# Microcontrolador.net
KiCad netlist of a schematic drawn in Altium Designer
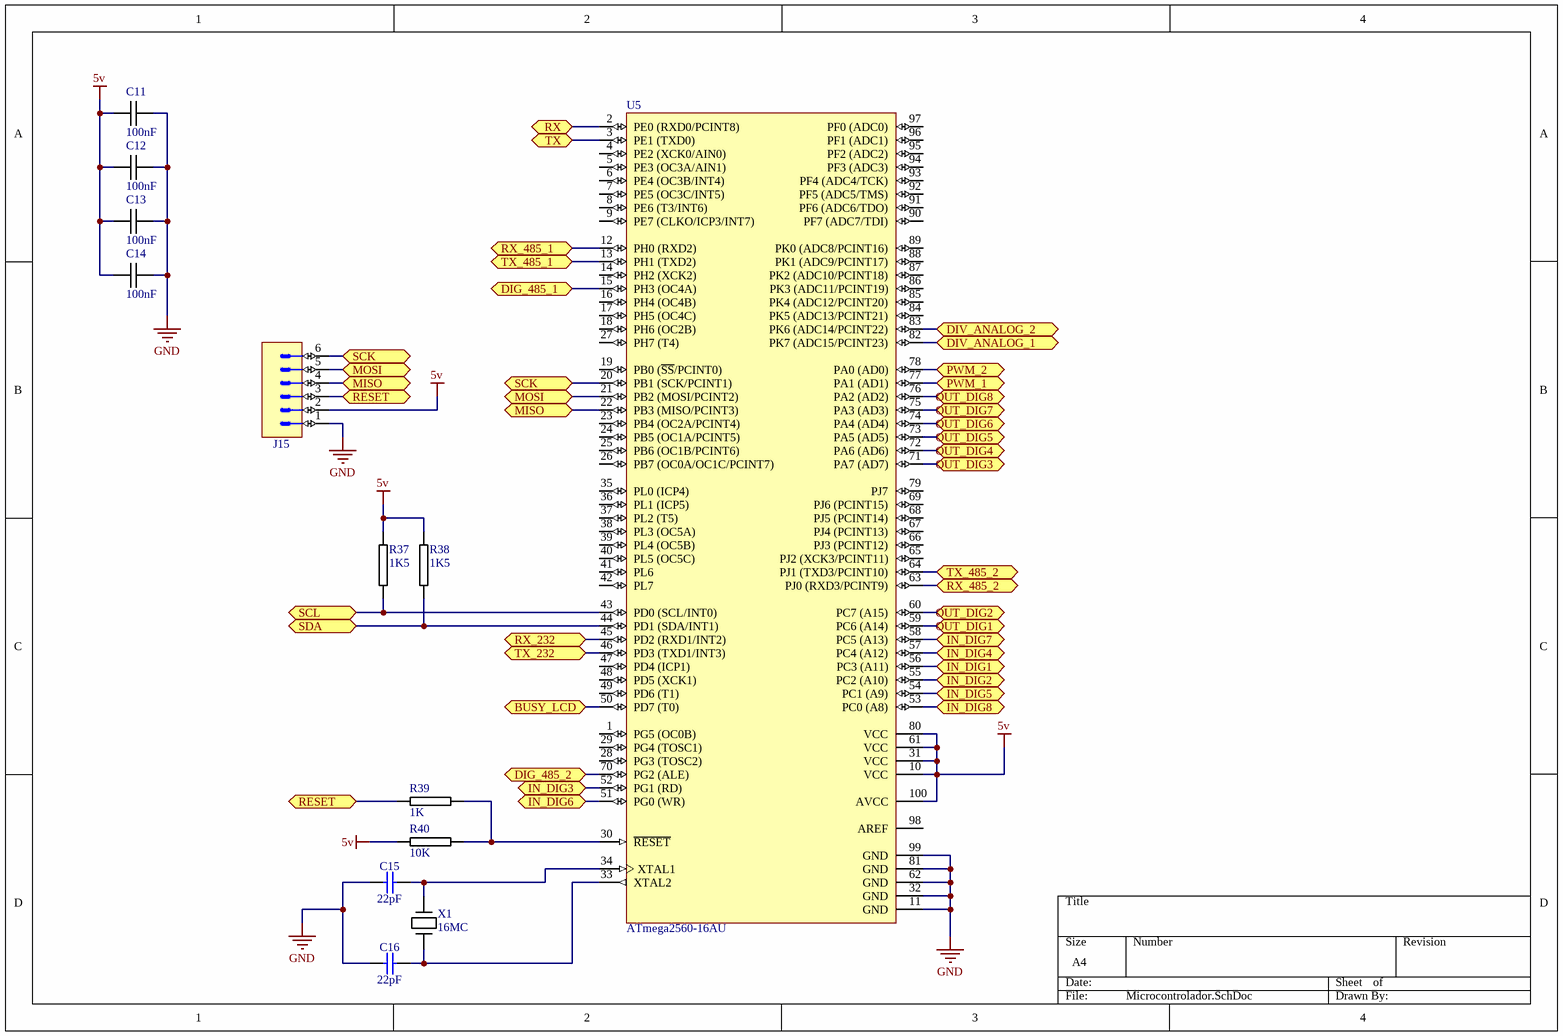
[diagram p0: Microcontrolador.SchDoc]

(export (version "E")
  (design (tool "Eeschema 10.0.6"))
  (components
    (comp (ref "C11")
      (value "100nF")
      (footprint "0805C-TBD")
      (description "CAPACITOR 0805 CERAMIC")
      (libsource (lib "vh_altium_library") (part "0805C-100nF-25V-X7R-MUR"))
    )
    (comp (ref "C12")
      (value "100nF")
      (footprint "0805C-TBD")
      (description "CAPACITOR 0805 CERAMIC")
      (libsource (lib "vh_altium_library") (part "0805C-100nF-25V-X7R-MUR"))
    )
    (comp (ref "C13")
      (value "100nF")
      (footprint "0805C-TBD")
      (description "CAPACITOR 0805 CERAMIC")
      (libsource (lib "vh_altium_library") (part "0805C-100nF-25V-X7R-MUR"))
    )
    (comp (ref "C14")
      (value "100nF")
      (footprint "0805C-TBD")
      (description "CAPACITOR 0805 CERAMIC")
      (libsource (lib "vh_altium_library") (part "0805C-100nF-25V-X7R-MUR"))
    )
    (comp (ref "C15")
      (value "22pF")
      (footprint "CAPC2012X135N")
      (description "Non-polarised capacitor")
      (fields
        (field (name "PART NUMBER") "CC0805_22PF_50V_5%_NP0")
        (field (name "VOLTAGE") "50V")
        (field (name "AUTHOR") "CERN DEM JLC")
      )
      (libsource (lib "Capacitors") (part "Capacitor - non polarized"))
    )
    (comp (ref "C16")
      (value "22pF")
      (footprint "CAPC2012X135N")
      (description "Non-polarised capacitor")
      (fields
        (field (name "PART NUMBER") "CC0805_22PF_50V_5%_NP0")
        (field (name "VOLTAGE") "50V")
        (field (name "AUTHOR") "CERN DEM JLC")
      )
      (libsource (lib "Capacitors") (part "Capacitor - non polarized"))
    )
    (comp (ref "J15")
      (value "KK®")
      (footprint "MOLEX_22-27-2061")
      (description "Connector 6 Male")
      (fields
        (field (name "PART NUMBER") "MOLEX_22-27-2061")
        (field (name "MANUFACTURER") "MOLEX")
        (field (name "AUTHOR") "CERN DEM JMW")
      )
      (libsource (lib "Connectors") (part "Connector 6 Male"))
    )
    (comp (ref "R37")
      (value "1K5")
      (footprint "0805R-1K5")
      (description "RESISTOR 0805 1/4 WATT THIN FILM")
      (libsource (lib "vh_altium_library") (part "0805R-1K5"))
    )
    (comp (ref "R38")
      (value "1K5")
      (footprint "0805R-1K5")
      (description "RESISTOR 0805 1/4 WATT THIN FILM")
      (libsource (lib "vh_altium_library") (part "0805R-1K5"))
    )
    (comp (ref "R39")
      (value "1K")
      (footprint "0805R-1K")
      (description "RESISTOR 0805 1/4 WATT THIN FILM")
      (libsource (lib "vh_altium_library") (part "0805R-1K"))
    )
    (comp (ref "R40")
      (value "10K")
      (footprint "0805R-10K")
      (description "RESISTOR 0805 1/4 WATT THIN FILM")
      (libsource (lib "vh_altium_library") (part "0805R-10K"))
    )
    (comp (ref "U5")
      (value "ATmega2560-16AU")
      (footprint "100A_N")
      (libsource (lib "Atmel Microcontroller megaAVR") (part "ATmega2560-16AU"))
    )
    (comp (ref "X1")
      (value "16MC")
      (footprint "XTAL-RU49/4")
      (description "16MHZ CRSYTAL HC49US")
      (libsource (lib "vh_altium_library") (part "16MC-HC49US"))
    )
  )
  (nets
    (net (code "1") (name "/BUSY_LCD") (class "Default")
      (node (ref "U5") (pin "50") (pinfunction "PD7_(T0)_50") (pintype "bidirectional"))
    )
    (net (code "2") (name "/DIG_485_1") (class "Default")
      (node (ref "U5") (pin "15") (pinfunction "PH3_(OC4A)_15") (pintype "bidirectional"))
    )
    (net (code "3") (name "/DIG_485_2") (class "Default")
      (node (ref "U5") (pin "70") (pinfunction "PG2_(ALE)_70") (pintype "bidirectional"))
    )
    (net (code "4") (name "/DIV_ANALOG_1") (class "Default")
      (node (ref "U5") (pin "82") (pinfunction "PK7_(ADC15/PCINT23)_82") (pintype "bidirectional"))
    )
    (net (code "5") (name "/DIV_ANALOG_2") (class "Default")
      (node (ref "U5") (pin "83") (pinfunction "PK6_(ADC14/PCINT22)_83") (pintype "bidirectional"))
    )
    (net (code "6") (name "/IN_DIG1") (class "Default")
      (node (ref "U5") (pin "56") (pinfunction "PC3_(A11)_56") (pintype "bidirectional"))
    )
    (net (code "7") (name "/IN_DIG2") (class "Default")
      (node (ref "U5") (pin "55") (pinfunction "PC2_(A10)_55") (pintype "bidirectional"))
    )
    (net (code "8") (name "/IN_DIG3") (class "Default")
      (node (ref "U5") (pin "52") (pinfunction "PG1_(RD)_52") (pintype "bidirectional"))
    )
    (net (code "9") (name "/IN_DIG4") (class "Default")
      (node (ref "U5") (pin "57") (pinfunction "PC4_(A12)_57") (pintype "bidirectional"))
    )
    (net (code "10") (name "/IN_DIG5") (class "Default")
      (node (ref "U5") (pin "54") (pinfunction "PC1_(A9)_54") (pintype "bidirectional"))
    )
    (net (code "11") (name "/IN_DIG6") (class "Default")
      (node (ref "U5") (pin "51") (pinfunction "PG0_(WR)_51") (pintype "bidirectional"))
    )
    (net (code "12") (name "/IN_DIG7") (class "Default")
      (node (ref "U5") (pin "58") (pinfunction "PC5_(A13)_58") (pintype "bidirectional"))
    )
    (net (code "13") (name "/IN_DIG8") (class "Default")
      (node (ref "U5") (pin "53") (pinfunction "PC0_(A8)_53") (pintype "bidirectional"))
    )
    (net (code "14") (name "/MISO") (class "Default")
      (node (ref "J15") (pin "4") (pinfunction "4_4") (pintype "bidirectional"))
      (node (ref "U5") (pin "22") (pinfunction "PB3_(MISO/PCINT3)_22") (pintype "bidirectional"))
    )
    (net (code "15") (name "/MOSI") (class "Default")
      (node (ref "J15") (pin "5") (pinfunction "5_5") (pintype "bidirectional"))
      (node (ref "U5") (pin "21") (pinfunction "PB2_(MOSI/PCINT2)_21") (pintype "bidirectional"))
    )
    (net (code "16") (name "/OUT_DIG1") (class "Default")
      (node (ref "U5") (pin "59") (pinfunction "PC6_(A14)_59") (pintype "bidirectional"))
    )
    (net (code "17") (name "/OUT_DIG2") (class "Default")
      (node (ref "U5") (pin "60") (pinfunction "PC7_(A15)_60") (pintype "bidirectional"))
    )
    (net (code "18") (name "/OUT_DIG3") (class "Default")
      (node (ref "U5") (pin "71") (pinfunction "PA7_(AD7)_71") (pintype "bidirectional"))
    )
    (net (code "19") (name "/OUT_DIG4") (class "Default")
      (node (ref "U5") (pin "72") (pinfunction "PA6_(AD6)_72") (pintype "bidirectional"))
    )
    (net (code "20") (name "/OUT_DIG5") (class "Default")
      (node (ref "U5") (pin "73") (pinfunction "PA5_(AD5)_73") (pintype "bidirectional"))
    )
    (net (code "21") (name "/OUT_DIG6") (class "Default")
      (node (ref "U5") (pin "74") (pinfunction "PA4_(AD4)_74") (pintype "bidirectional"))
    )
    (net (code "22") (name "/OUT_DIG7") (class "Default")
      (node (ref "U5") (pin "75") (pinfunction "PA3_(AD3)_75") (pintype "bidirectional"))
    )
    (net (code "23") (name "/OUT_DIG8") (class "Default")
      (node (ref "U5") (pin "76") (pinfunction "PA2_(AD2)_76") (pintype "bidirectional"))
    )
    (net (code "24") (name "/PWM_1") (class "Default")
      (node (ref "U5") (pin "77") (pinfunction "PA1_(AD1)_77") (pintype "bidirectional"))
    )
    (net (code "25") (name "/PWM_2") (class "Default")
      (node (ref "U5") (pin "78") (pinfunction "PA0_(AD0)_78") (pintype "bidirectional"))
    )
    (net (code "26") (name "/RESET") (class "Default")
      (node (ref "J15") (pin "3") (pinfunction "3_3") (pintype "bidirectional"))
      (node (ref "R39") (pin "1") (pintype "passive"))
    )
    (net (code "27") (name "/RX") (class "Default")
      (node (ref "U5") (pin "2") (pinfunction "PE0_(RXD0/PCINT8)_2") (pintype "bidirectional"))
    )
    (net (code "28") (name "/RX_232") (class "Default")
      (node (ref "U5") (pin "45") (pinfunction "PD2_(RXD1/INT2)_45") (pintype "bidirectional"))
    )
    (net (code "29") (name "/RX_485_1") (class "Default")
      (node (ref "U5") (pin "12") (pinfunction "PH0_(RXD2)_12") (pintype "bidirectional"))
    )
    (net (code "30") (name "/RX_485_2") (class "Default")
      (node (ref "U5") (pin "63") (pinfunction "PJ0_(RXD3/PCINT9)_63") (pintype "bidirectional"))
    )
    (net (code "31") (name "/SCK") (class "Default")
      (node (ref "J15") (pin "6") (pinfunction "6_6") (pintype "bidirectional"))
      (node (ref "U5") (pin "20") (pinfunction "PB1_(SCK/PCINT1)_20") (pintype "bidirectional"))
    )
    (net (code "32") (name "/SCL") (class "Default")
      (node (ref "R37") (pin "2") (pintype "passive"))
      (node (ref "U5") (pin "43") (pinfunction "PD0_(SCL/INT0)_43") (pintype "bidirectional"))
    )
    (net (code "33") (name "/SDA") (class "Default")
      (node (ref "R38") (pin "2") (pintype "passive"))
      (node (ref "U5") (pin "44") (pinfunction "PD1_(SDA/INT1)_44") (pintype "bidirectional"))
    )
    (net (code "34") (name "/TX") (class "Default")
      (node (ref "U5") (pin "3") (pinfunction "PE1_(TXD0)_3") (pintype "bidirectional"))
    )
    (net (code "35") (name "/TX_232") (class "Default")
      (node (ref "U5") (pin "46") (pinfunction "PD3_(TXD1/INT3)_46") (pintype "bidirectional"))
    )
    (net (code "36") (name "/TX_485_1") (class "Default")
      (node (ref "U5") (pin "13") (pinfunction "PH1_(TXD2)_13") (pintype "bidirectional"))
    )
    (net (code "37") (name "/TX_485_2") (class "Default")
      (node (ref "U5") (pin "64") (pinfunction "PJ1_(TXD3/PCINT10)_64") (pintype "bidirectional"))
    )
    (net (code "38") (name "5v") (class "Default")
      (node (ref "C11") (pin "1") (pintype "passive"))
      (node (ref "C12") (pin "1") (pintype "passive"))
      (node (ref "C13") (pin "1") (pintype "passive"))
      (node (ref "C14") (pin "1") (pintype "passive"))
      (node (ref "J15") (pin "2") (pinfunction "2_2") (pintype "bidirectional"))
      (node (ref "R37") (pin "1") (pintype "passive"))
      (node (ref "R38") (pin "1") (pintype "passive"))
      (node (ref "R40") (pin "1") (pintype "passive"))
      (node (ref "U5") (pin "10") (pinfunction "VCC_10") (pintype "power_in"))
      (node (ref "U5") (pin "100") (pinfunction "AVCC_100") (pintype "power_in"))
      (node (ref "U5") (pin "31") (pinfunction "VCC_31") (pintype "power_in"))
      (node (ref "U5") (pin "61") (pinfunction "VCC_61") (pintype "power_in"))
      (node (ref "U5") (pin "80") (pinfunction "VCC_80") (pintype "power_in"))
    )
    (net (code "39") (name "GND") (class "Default")
      (node (ref "C11") (pin "2") (pintype "passive"))
      (node (ref "C12") (pin "2") (pintype "passive"))
      (node (ref "C13") (pin "2") (pintype "passive"))
      (node (ref "C14") (pin "2") (pintype "passive"))
      (node (ref "C15") (pin "1") (pinfunction "1_1") (pintype "passive"))
      (node (ref "C16") (pin "1") (pinfunction "1_1") (pintype "passive"))
      (node (ref "J15") (pin "1") (pinfunction "1_1") (pintype "bidirectional"))
      (node (ref "U5") (pin "11") (pinfunction "GND_11") (pintype "power_in"))
      (node (ref "U5") (pin "32") (pinfunction "GND_32") (pintype "power_in"))
      (node (ref "U5") (pin "62") (pinfunction "GND_62") (pintype "power_in"))
      (node (ref "U5") (pin "81") (pinfunction "GND_81") (pintype "power_in"))
      (node (ref "U5") (pin "99") (pinfunction "GND_99") (pintype "power_in"))
    )
    (net (code "40") (name "Net-(U5-XTAL1)") (class "Default")
      (node (ref "C15") (pin "2") (pinfunction "2_2") (pintype "passive"))
      (node (ref "U5") (pin "34") (pinfunction "XTAL1_34") (pintype "input"))
      (node (ref "X1") (pin "1") (pintype "passive"))
    )
    (net (code "41") (name "Net-(U5-XTAL2)") (class "Default")
      (node (ref "C16") (pin "2") (pinfunction "2_2") (pintype "passive"))
      (node (ref "U5") (pin "33") (pinfunction "XTAL2_33") (pintype "output"))
      (node (ref "X1") (pin "2") (pintype "passive"))
    )
    (net (code "42") (name "Net-(U5-~{RESET})") (class "Default")
      (node (ref "R39") (pin "2") (pintype "passive"))
      (node (ref "R40") (pin "2") (pintype "passive"))
      (node (ref "U5") (pin "30") (pinfunction "~{RESET}_30") (pintype "input"))
    )
    (net (code "43") (name "unconnected-(U5-AREF-Pad98)") (class "Default")
      (node (ref "U5") (pin "98") (pinfunction "AREF_98") (pintype "power_in"))
    )
    (net (code "44") (name "unconnected-(U5-PB0_(~{SS}{slash}PCINT0)-Pad19)") (class "Default")
      (node (ref "U5") (pin "19") (pinfunction "PB0_(~{SS}/PCINT0)_19") (pintype "bidirectional"))
    )
    (net (code "45") (name "unconnected-(U5-PB4_(OC2A{slash}PCINT4)-Pad23)") (class "Default")
      (node (ref "U5") (pin "23") (pinfunction "PB4_(OC2A/PCINT4)_23") (pintype "bidirectional"))
    )
    (net (code "46") (name "unconnected-(U5-PB5_(OC1A{slash}PCINT5)-Pad24)") (class "Default")
      (node (ref "U5") (pin "24") (pinfunction "PB5_(OC1A/PCINT5)_24") (pintype "bidirectional"))
    )
    (net (code "47") (name "unconnected-(U5-PB6_(OC1B{slash}PCINT6)-Pad25)") (class "Default")
      (node (ref "U5") (pin "25") (pinfunction "PB6_(OC1B/PCINT6)_25") (pintype "bidirectional"))
    )
    (net (code "48") (name "unconnected-(U5-PB7_(OC0A{slash}OC1C{slash}PCINT7)-Pad26)") (class "Default")
      (node (ref "U5") (pin "26") (pinfunction "PB7_(OC0A/OC1C/PCINT7)_26") (pintype "bidirectional"))
    )
    (net (code "49") (name "unconnected-(U5-PD4_(ICP1)-Pad47)") (class "Default")
      (node (ref "U5") (pin "47") (pinfunction "PD4_(ICP1)_47") (pintype "bidirectional"))
    )
    (net (code "50") (name "unconnected-(U5-PD5_(XCK1)-Pad48)") (class "Default")
      (node (ref "U5") (pin "48") (pinfunction "PD5_(XCK1)_48") (pintype "bidirectional"))
    )
    (net (code "51") (name "unconnected-(U5-PD6_(T1)-Pad49)") (class "Default")
      (node (ref "U5") (pin "49") (pinfunction "PD6_(T1)_49") (pintype "bidirectional"))
    )
    (net (code "52") (name "unconnected-(U5-PE2_(XCK0{slash}AIN0)-Pad4)") (class "Default")
      (node (ref "U5") (pin "4") (pinfunction "PE2_(XCK0/AIN0)_4") (pintype "bidirectional"))
    )
    (net (code "53") (name "unconnected-(U5-PE3_(OC3A{slash}AIN1)-Pad5)") (class "Default")
      (node (ref "U5") (pin "5") (pinfunction "PE3_(OC3A/AIN1)_5") (pintype "bidirectional"))
    )
    (net (code "54") (name "unconnected-(U5-PE4_(OC3B{slash}INT4)-Pad6)") (class "Default")
      (node (ref "U5") (pin "6") (pinfunction "PE4_(OC3B/INT4)_6") (pintype "bidirectional"))
    )
    (net (code "55") (name "unconnected-(U5-PE5_(OC3C{slash}INT5)-Pad7)") (class "Default")
      (node (ref "U5") (pin "7") (pinfunction "PE5_(OC3C/INT5)_7") (pintype "bidirectional"))
    )
    (net (code "56") (name "unconnected-(U5-PE6_(T3{slash}INT6)-Pad8)") (class "Default")
      (node (ref "U5") (pin "8") (pinfunction "PE6_(T3/INT6)_8") (pintype "bidirectional"))
    )
    (net (code "57") (name "unconnected-(U5-PE7_(CLKO{slash}ICP3{slash}INT7)-Pad9)") (class "Default")
      (node (ref "U5") (pin "9") (pinfunction "PE7_(CLKO/ICP3/INT7)_9") (pintype "bidirectional"))
    )
    (net (code "58") (name "unconnected-(U5-PF0_(ADC0)-Pad97)") (class "Default")
      (node (ref "U5") (pin "97") (pinfunction "PF0_(ADC0)_97") (pintype "bidirectional"))
    )
    (net (code "59") (name "unconnected-(U5-PF1_(ADC1)-Pad96)") (class "Default")
      (node (ref "U5") (pin "96") (pinfunction "PF1_(ADC1)_96") (pintype "bidirectional"))
    )
    (net (code "60") (name "unconnected-(U5-PF2_(ADC2)-Pad95)") (class "Default")
      (node (ref "U5") (pin "95") (pinfunction "PF2_(ADC2)_95") (pintype "bidirectional"))
    )
    (net (code "61") (name "unconnected-(U5-PF3_(ADC3)-Pad94)") (class "Default")
      (node (ref "U5") (pin "94") (pinfunction "PF3_(ADC3)_94") (pintype "bidirectional"))
    )
    (net (code "62") (name "unconnected-(U5-PF4_(ADC4{slash}TCK)-Pad93)") (class "Default")
      (node (ref "U5") (pin "93") (pinfunction "PF4_(ADC4/TCK)_93") (pintype "bidirectional"))
    )
    (net (code "63") (name "unconnected-(U5-PF5_(ADC5{slash}TMS)-Pad92)") (class "Default")
      (node (ref "U5") (pin "92") (pinfunction "PF5_(ADC5/TMS)_92") (pintype "bidirectional"))
    )
    (net (code "64") (name "unconnected-(U5-PF6_(ADC6{slash}TDO)-Pad91)") (class "Default")
      (node (ref "U5") (pin "91") (pinfunction "PF6_(ADC6/TDO)_91") (pintype "bidirectional"))
    )
    (net (code "65") (name "unconnected-(U5-PF7_(ADC7{slash}TDI)-Pad90)") (class "Default")
      (node (ref "U5") (pin "90") (pinfunction "PF7_(ADC7/TDI)_90") (pintype "bidirectional"))
    )
    (net (code "66") (name "unconnected-(U5-PG3_(TOSC2)-Pad28)") (class "Default")
      (node (ref "U5") (pin "28") (pinfunction "PG3_(TOSC2)_28") (pintype "bidirectional"))
    )
    (net (code "67") (name "unconnected-(U5-PG4_(TOSC1)-Pad29)") (class "Default")
      (node (ref "U5") (pin "29") (pinfunction "PG4_(TOSC1)_29") (pintype "bidirectional"))
    )
    (net (code "68") (name "unconnected-(U5-PG5_(OC0B)-Pad1)") (class "Default")
      (node (ref "U5") (pin "1") (pinfunction "PG5_(OC0B)_1") (pintype "bidirectional"))
    )
    (net (code "69") (name "unconnected-(U5-PH2_(XCK2)-Pad14)") (class "Default")
      (node (ref "U5") (pin "14") (pinfunction "PH2_(XCK2)_14") (pintype "bidirectional"))
    )
    (net (code "70") (name "unconnected-(U5-PH4_(OC4B)-Pad16)") (class "Default")
      (node (ref "U5") (pin "16") (pinfunction "PH4_(OC4B)_16") (pintype "bidirectional"))
    )
    (net (code "71") (name "unconnected-(U5-PH5_(OC4C)-Pad17)") (class "Default")
      (node (ref "U5") (pin "17") (pinfunction "PH5_(OC4C)_17") (pintype "bidirectional"))
    )
    (net (code "72") (name "unconnected-(U5-PH6_(OC2B)-Pad18)") (class "Default")
      (node (ref "U5") (pin "18") (pinfunction "PH6_(OC2B)_18") (pintype "bidirectional"))
    )
    (net (code "73") (name "unconnected-(U5-PH7_(T4)-Pad27)") (class "Default")
      (node (ref "U5") (pin "27") (pinfunction "PH7_(T4)_27") (pintype "bidirectional"))
    )
    (net (code "74") (name "unconnected-(U5-PJ2_(XCK3{slash}PCINT11)-Pad65)") (class "Default")
      (node (ref "U5") (pin "65") (pinfunction "PJ2_(XCK3/PCINT11)_65") (pintype "bidirectional"))
    )
    (net (code "75") (name "unconnected-(U5-PJ3_(PCINT12)-Pad66)") (class "Default")
      (node (ref "U5") (pin "66") (pinfunction "PJ3_(PCINT12)_66") (pintype "bidirectional"))
    )
    (net (code "76") (name "unconnected-(U5-PJ4_(PCINT13)-Pad67)") (class "Default")
      (node (ref "U5") (pin "67") (pinfunction "PJ4_(PCINT13)_67") (pintype "bidirectional"))
    )
    (net (code "77") (name "unconnected-(U5-PJ5_(PCINT14)-Pad68)") (class "Default")
      (node (ref "U5") (pin "68") (pinfunction "PJ5_(PCINT14)_68") (pintype "bidirectional"))
    )
    (net (code "78") (name "unconnected-(U5-PJ6_(PCINT15)-Pad69)") (class "Default")
      (node (ref "U5") (pin "69") (pinfunction "PJ6_(PCINT15)_69") (pintype "bidirectional"))
    )
    (net (code "79") (name "unconnected-(U5-PJ7-Pad79)") (class "Default")
      (node (ref "U5") (pin "79") (pinfunction "PJ7_79") (pintype "bidirectional"))
    )
    (net (code "80") (name "unconnected-(U5-PK0_(ADC8{slash}PCINT16)-Pad89)") (class "Default")
      (node (ref "U5") (pin "89") (pinfunction "PK0_(ADC8/PCINT16)_89") (pintype "bidirectional"))
    )
    (net (code "81") (name "unconnected-(U5-PK1_(ADC9{slash}PCINT17)-Pad88)") (class "Default")
      (node (ref "U5") (pin "88") (pinfunction "PK1_(ADC9/PCINT17)_88") (pintype "bidirectional"))
    )
    (net (code "82") (name "unconnected-(U5-PK2_(ADC10{slash}PCINT18)-Pad87)") (class "Default")
      (node (ref "U5") (pin "87") (pinfunction "PK2_(ADC10/PCINT18)_87") (pintype "bidirectional"))
    )
    (net (code "83") (name "unconnected-(U5-PK3_(ADC11{slash}PCINT19)-Pad86)") (class "Default")
      (node (ref "U5") (pin "86") (pinfunction "PK3_(ADC11/PCINT19)_86") (pintype "bidirectional"))
    )
    (net (code "84") (name "unconnected-(U5-PK4_(ADC12{slash}PCINT20)-Pad85)") (class "Default")
      (node (ref "U5") (pin "85") (pinfunction "PK4_(ADC12/PCINT20)_85") (pintype "bidirectional"))
    )
    (net (code "85") (name "unconnected-(U5-PK5_(ADC13{slash}PCINT21)-Pad84)") (class "Default")
      (node (ref "U5") (pin "84") (pinfunction "PK5_(ADC13/PCINT21)_84") (pintype "bidirectional"))
    )
    (net (code "86") (name "unconnected-(U5-PL0_(ICP4)-Pad35)") (class "Default")
      (node (ref "U5") (pin "35") (pinfunction "PL0_(ICP4)_35") (pintype "bidirectional"))
    )
    (net (code "87") (name "unconnected-(U5-PL1_(ICP5)-Pad36)") (class "Default")
      (node (ref "U5") (pin "36") (pinfunction "PL1_(ICP5)_36") (pintype "bidirectional"))
    )
    (net (code "88") (name "unconnected-(U5-PL2_(T5)-Pad37)") (class "Default")
      (node (ref "U5") (pin "37") (pinfunction "PL2_(T5)_37") (pintype "bidirectional"))
    )
    (net (code "89") (name "unconnected-(U5-PL3_(OC5A)-Pad38)") (class "Default")
      (node (ref "U5") (pin "38") (pinfunction "PL3_(OC5A)_38") (pintype "bidirectional"))
    )
    (net (code "90") (name "unconnected-(U5-PL4_(OC5B)-Pad39)") (class "Default")
      (node (ref "U5") (pin "39") (pinfunction "PL4_(OC5B)_39") (pintype "bidirectional"))
    )
    (net (code "91") (name "unconnected-(U5-PL5_(OC5C)-Pad40)") (class "Default")
      (node (ref "U5") (pin "40") (pinfunction "PL5_(OC5C)_40") (pintype "bidirectional"))
    )
    (net (code "92") (name "unconnected-(U5-PL6-Pad41)") (class "Default")
      (node (ref "U5") (pin "41") (pinfunction "PL6_41") (pintype "bidirectional"))
    )
    (net (code "93") (name "unconnected-(U5-PL7-Pad42)") (class "Default")
      (node (ref "U5") (pin "42") (pinfunction "PL7_42") (pintype "bidirectional"))
    )
  )
)
